# NQX25017A-V1_0_i300-N32WB031.net
KiCad netlist of a schematic drawn in Altium Designer
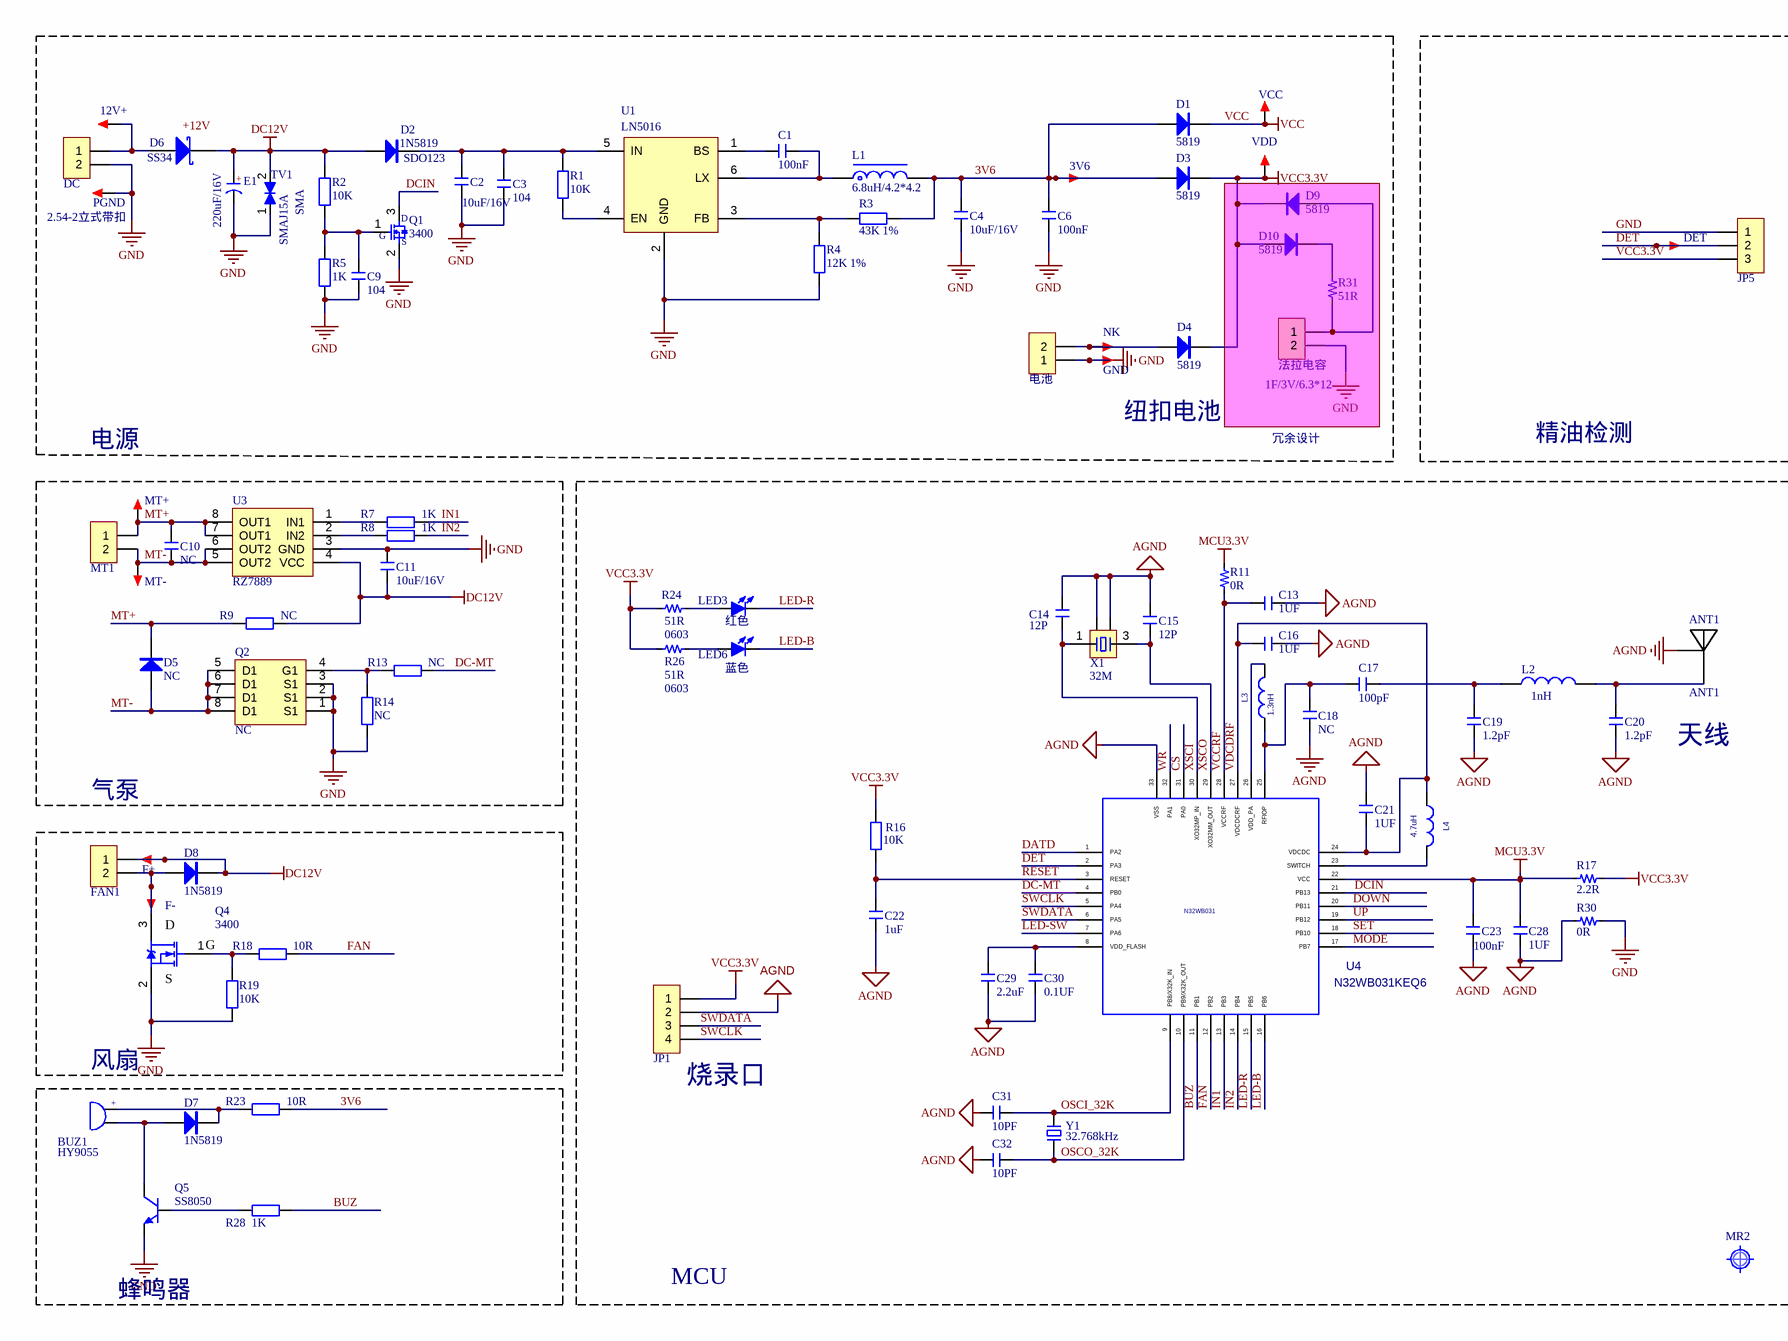
[diagram p0: NQX25017A-V1.0(i300-N32WB031).SchDoc, left]
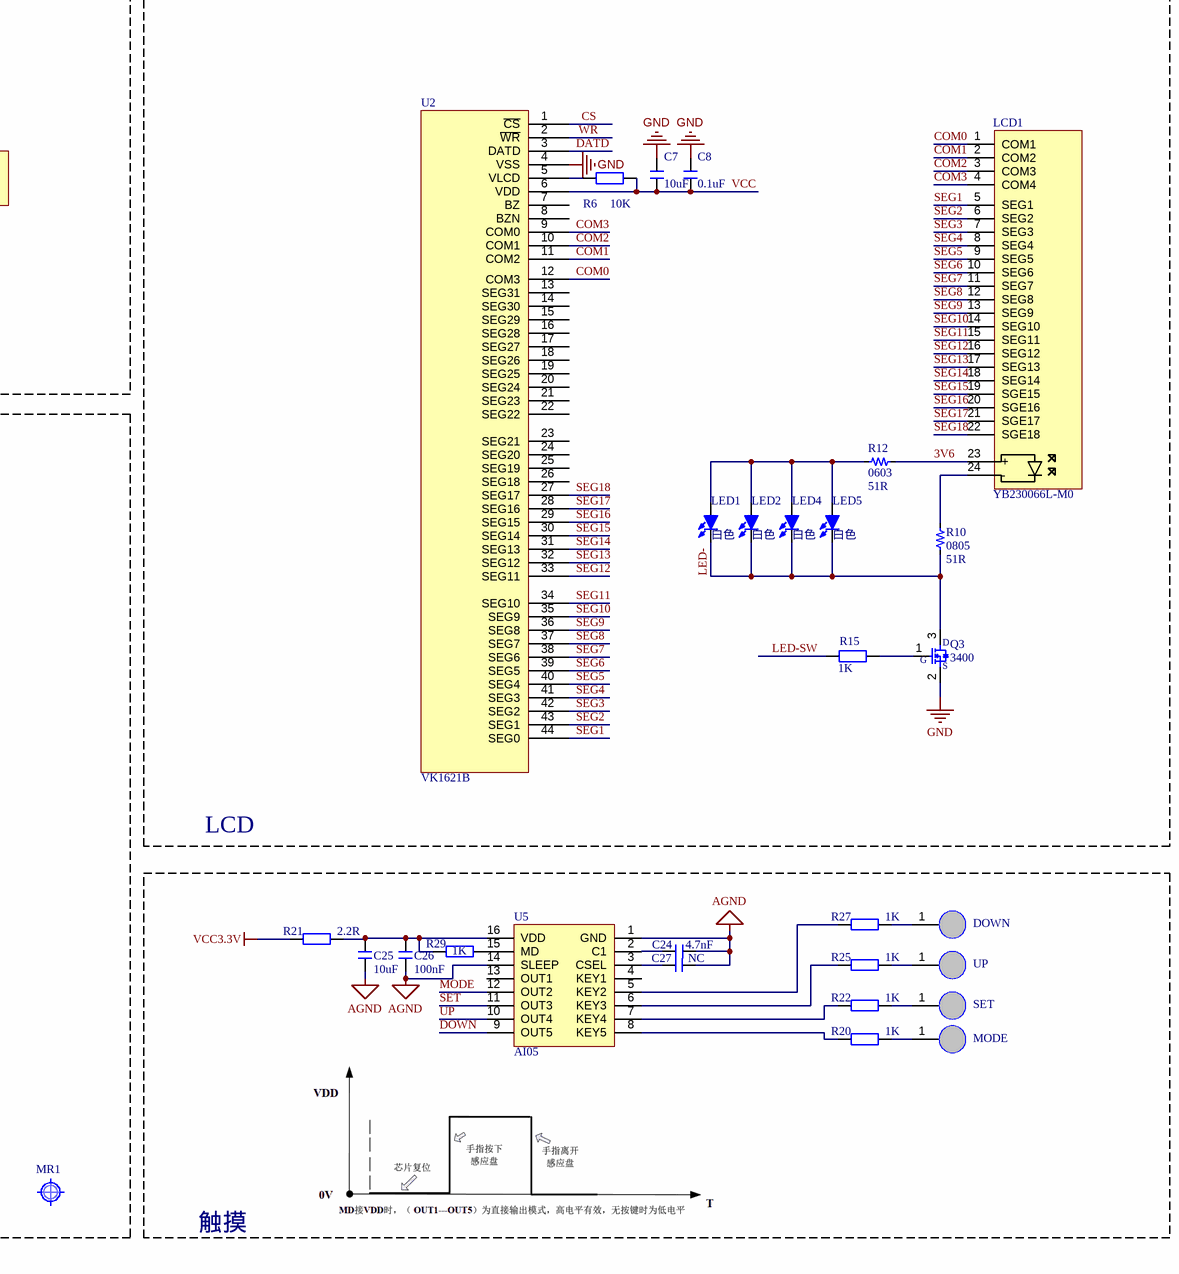
[diagram p1: NQX25017A-V1.0(i300-N32WB031).SchDoc, right]

(export (version "E")
  (design (tool "Eeschema 10.0.6"))
  (components
    (comp (ref "3V6")
      (value "TEST")
      (footprint "TEST 1.2")
      (description "测试点")
      (fields (field (name "版权归属") "封装库来自淘宝 ID：黄晶宝石"))
      (libsource (lib "4.1 - 未分类器件") (part "TEST"))
    )
    (comp (ref "12V+")
      (value "TEST")
      (footprint "TEST 1.2")
      (description "测试点")
      (fields (field (name "版权归属") "封装库来自淘宝 ID：黄晶宝石"))
      (libsource (lib "4.1 - 未分类器件") (part "TEST"))
    )
    (comp (ref "ANT1")
      (value "ANT1")
      (footprint "ANT-BLUE")
      (description "PCB板载天线")
      (fields (field (name "版权归属") "封装库来自淘宝 ID：黄晶宝石"))
      (libsource (lib "1.8 - WiFi天线-SMA射频座") (part "ANT2_1"))
    )
    (comp (ref "BUZ1")
      (value "HY9055")
      (footprint "BEEP 4x9x5.5 - duplicate")
      (description "蜂鸣器")
      (fields (field (name "版权归属") "封装库来自淘宝 ID：黄晶宝石"))
      (libsource (lib "4.1 - 未分类器件") (part "BEEP"))
    )
    (comp (ref "C1")
      (value "100nF")
      (footprint "C0603-T")
      (description "贴片电容")
      (libsource (lib "0.1 - 电阻-电容-电感") (part "C"))
    )
    (comp (ref "C2")
      (value "10uF/16V")
      (footprint "C0603")
      (description "贴片电容")
      (libsource (lib "0.1 - 电阻-电容-电感") (part "C"))
    )
    (comp (ref "C3")
      (value "104")
      (footprint "C0603-T")
      (description "贴片电容")
      (libsource (lib "0.1 - 电阻-电容-电感") (part "C"))
    )
    (comp (ref "C4")
      (value "10uF/16V")
      (footprint "C0805-T")
      (description "贴片电容")
      (libsource (lib "0.1 - 电阻-电容-电感") (part "C"))
    )
    (comp (ref "C6")
      (value "100nF")
      (footprint "C0603-T")
      (description "贴片电容")
      (libsource (lib "0.1 - 电阻-电容-电感") (part "C"))
    )
    (comp (ref "C7")
      (value "10uF")
      (footprint "C0603-T")
      (description "贴片电容")
      (libsource (lib "0.1 - 电阻-电容-电感") (part "C"))
    )
    (comp (ref "C8")
      (value "0.1uF")
      (footprint "C0603-T")
      (description "贴片电容")
      (libsource (lib "0.1 - 电阻-电容-电感") (part "C"))
    )
    (comp (ref "C9")
      (value "104")
      (footprint "C0603-T")
      (description "贴片电容")
      (libsource (lib "0.1 - 电阻-电容-电感") (part "C"))
    )
    (comp (ref "C10")
      (value "NC")
      (footprint "C0603-T")
      (description "贴片电容")
      (libsource (lib "0.1 - 电阻-电容-电感") (part "C"))
    )
    (comp (ref "C11")
      (value "10uF/16V")
      (footprint "C0603")
      (description "贴片电容")
      (libsource (lib "0.1 - 电阻-电容-电感") (part "C"))
    )
    (comp (ref "C13")
      (value "1UF")
      (footprint "C0603-T")
      (description "贴片电容")
      (libsource (lib "0.1 - 电阻-电容-电感") (part "C"))
    )
    (comp (ref "C14")
      (value "12P")
      (footprint "C0603-T")
      (description "贴片电容")
      (libsource (lib "0.1 - 电阻-电容-电感") (part "C"))
    )
    (comp (ref "C15")
      (value "12P")
      (footprint "C0603-T")
      (description "贴片电容")
      (libsource (lib "0.1 - 电阻-电容-电感") (part "C"))
    )
    (comp (ref "C16")
      (value "1UF")
      (footprint "C0603-T")
      (description "贴片电容")
      (libsource (lib "0.1 - 电阻-电容-电感") (part "C"))
    )
    (comp (ref "C17")
      (value "100pF")
      (footprint "C0603-T")
      (description "贴片电容")
      (libsource (lib "0.1 - 电阻-电容-电感") (part "C"))
    )
    (comp (ref "C18")
      (value "NC")
      (footprint "C0603-T")
      (description "贴片电容")
      (libsource (lib "0.1 - 电阻-电容-电感") (part "C"))
    )
    (comp (ref "C19")
      (value "1.2pF")
      (footprint "C0603-T")
      (description "贴片电容")
      (libsource (lib "0.1 - 电阻-电容-电感") (part "C"))
    )
    (comp (ref "C20")
      (value "1.2pF")
      (footprint "C0603-T")
      (description "贴片电容")
      (libsource (lib "0.1 - 电阻-电容-电感") (part "C"))
    )
    (comp (ref "C21")
      (value "1UF")
      (footprint "C0603-T")
      (description "贴片电容")
      (libsource (lib "0.1 - 电阻-电容-电感") (part "C"))
    )
    (comp (ref "C22")
      (value "1uF")
      (footprint "C0603-T")
      (description "贴片电容")
      (libsource (lib "0.1 - 电阻-电容-电感") (part "C"))
    )
    (comp (ref "C23")
      (value "100nF")
      (footprint "C0603-T")
      (description "贴片电容")
      (libsource (lib "0.1 - 电阻-电容-电感") (part "C"))
    )
    (comp (ref "C24")
      (value "4.7nF")
      (footprint "C0603-T")
      (description "贴片电容")
      (libsource (lib "0.1 - 电阻-电容-电感") (part "C"))
    )
    (comp (ref "C25")
      (value "10uF")
      (footprint "C0603-T")
      (description "贴片电容")
      (libsource (lib "0.1 - 电阻-电容-电感") (part "C"))
    )
    (comp (ref "C26")
      (value "100nF")
      (footprint "C0603-T")
      (description "贴片电容")
      (libsource (lib "0.1 - 电阻-电容-电感") (part "C"))
    )
    (comp (ref "C27")
      (value "NC")
      (footprint "C0603-T")
      (description "贴片电容")
      (libsource (lib "0.1 - 电阻-电容-电感") (part "C"))
    )
    (comp (ref "C28")
      (value "1UF")
      (footprint "C0603-T")
      (description "贴片电容")
      (libsource (lib "0.1 - 电阻-电容-电感") (part "C"))
    )
    (comp (ref "C29")
      (value "2.2uF")
      (footprint "C0603-T")
      (description "贴片电容")
      (libsource (lib "0.1 - 电阻-电容-电感") (part "C"))
    )
    (comp (ref "C30")
      (value "0.1UF")
      (footprint "C0603-T")
      (description "贴片电容")
      (libsource (lib "0.1 - 电阻-电容-电感") (part "C"))
    )
    (comp (ref "C31")
      (value "10PF")
      (footprint "C0603-T")
      (description "贴片电容")
      (libsource (lib "0.1 - 电阻-电容-电感") (part "C"))
    )
    (comp (ref "C32")
      (value "10PF")
      (footprint "C0603-T")
      (description "贴片电容")
      (libsource (lib "0.1 - 电阻-电容-电感") (part "C"))
    )
    (comp (ref "D1")
      (value "5819")
      (footprint "SOD-123")
      (description "整流二极管")
      (libsource (lib "0.2 - 二极管-整流桥") (part "1N4007"))
    )
    (comp (ref "D2")
      (value "1N5819")
      (footprint "SOD-123")
      (description "整流二极管")
      (fields (field (name "ALTIUM_VALUE") "SDO123"))
      (libsource (lib "0.2 - 二极管-整流桥") (part "1N4007"))
    )
    (comp (ref "D3")
      (value "5819")
      (footprint "SOD-123")
      (description "整流二极管")
      (libsource (lib "0.2 - 二极管-整流桥") (part "1N4007"))
    )
    (comp (ref "D4")
      (value "5819")
      (footprint "SOD-123")
      (description "整流二极管")
      (libsource (lib "0.2 - 二极管-整流桥") (part "1N4007"))
    )
    (comp (ref "D5")
      (value "NC")
      (footprint "SMA")
      (description "整流二极管")
      (fields (field (name "版权归属") "封装库来自淘宝 ID：黄晶宝石"))
      (libsource (lib "0.2 - 二极管-整流桥") (part "M7"))
    )
    (comp (ref "D6")
      (value "SS34")
      (footprint "SMA")
      (description "肖特基二极管")
      (libsource (lib "0.2 - 二极管-整流桥") (part "SS14"))
    )
    (comp (ref "D7")
      (value "1N5819")
      (footprint "MINI_MELF (LL34)")
      (description "开关二极管")
      (libsource (lib "0.2 - 二极管-整流桥") (part "1N4148"))
    )
    (comp (ref "D8")
      (value "1N5819")
      (footprint "MINI_MELF (LL34)")
      (description "开关二极管")
      (libsource (lib "0.2 - 二极管-整流桥") (part "1N4148"))
    )
    (comp (ref "D9")
      (value "5819")
      (footprint "SOD-123")
      (description "整流二极管")
      (libsource (lib "0.2 - 二极管-整流桥") (part "1N4007"))
    )
    (comp (ref "D10")
      (value "5819")
      (footprint "SOD-123")
      (description "整流二极管")
      (libsource (lib "0.2 - 二极管-整流桥") (part "1N4007"))
    )
    (comp (ref "DC")
      (value "2.54-2立式带扣")
      (footprint "XH2.54-LS-2P")
      (description "2P接插件")
      (fields (field (name "版权归属") "封装库来自淘宝 ID：黄晶宝石"))
      (libsource (lib "5.4 - 接插件-脚距2.54 (100mil) ") (part "Header 2"))
    )
    (comp (ref "DET")
      (value "TEST")
      (footprint "TEST 1.2")
      (description "测试点")
      (fields (field (name "版权归属") "封装库来自淘宝 ID：黄晶宝石"))
      (libsource (lib "4.1 - 未分类器件") (part "TEST"))
    )
    (comp (ref "DOWN")
      (value "12x16")
      (footprint "0.3-6.8-12-8")
      (description "触控弹簧")
      (fields (field (name "版权归属") "封装库来自淘宝 ID：黄晶宝石"))
      (libsource (lib "0.7 - 常用按键-开关") (part "TTS"))
    )
    (comp (ref "E1")
      (value "220uF/16V")
      (footprint "CM D(6.3*7.7)")
      (description "贴片电解电容")
      (fields (field (name "版权归属") "封装库来自淘宝 ID：黄晶宝石"))
      (libsource (lib "0.1 - 电阻-电容-电感") (part "CE_SMD"))
    )
    (comp (ref "F+")
      (value "TEST")
      (footprint "TEST 1.2")
      (description "测试点")
      (fields (field (name "版权归属") "封装库来自淘宝 ID：黄晶宝石"))
      (libsource (lib "4.1 - 未分类器件") (part "TEST"))
    )
    (comp (ref "F-")
      (value "TEST")
      (footprint "TEST 1.2")
      (description "测试点")
      (fields (field (name "版权归属") "封装库来自淘宝 ID：黄晶宝石"))
      (libsource (lib "4.1 - 未分类器件") (part "TEST"))
    )
    (comp (ref "FAN1")
      (value "2.54-2立式带扣")
      (footprint "XH2.54-LS-2P")
      (description "2P接插件")
      (fields (field (name "版权归属") "封装库来自淘宝 ID：黄晶宝石"))
      (libsource (lib "5.4 - 接插件-脚距2.54 (100mil) ") (part "Header 2"))
    )
    (comp (ref "GND")
      (value "TEST")
      (footprint "TEST 1.2")
      (description "测试点")
      (fields (field (name "版权归属") "封装库来自淘宝 ID：黄晶宝石"))
      (libsource (lib "4.1 - 未分类器件") (part "TEST"))
    )
    (comp (ref "JP1")
      (value "HDR-1X4")
      (footprint "CN4P2.0")
      (libsource (lib "5.4 - 接插件-脚距2.54 (100mil) ") (part "Header 4"))
    )
    (comp (ref "JP5")
      (value "1.25X3立贴")
      (footprint "MX 1.25-LS-3P")
      (description "3P接插件")
      (libsource (lib "5.0 - 接插件-脚距1.25") (part "Header 3"))
    )
    (comp (ref "L1")
      (value "6.8uH/4.2*4.2")
      (footprint "L5X5")
      (description "CD系列贴片线绕功率电感")
      (libsource (lib "0.1 - 电阻-电容-电感") (part "L-SMD"))
    )
    (comp (ref "L2")
      (value "1nH")
      (footprint "R0603-T")
      (description "小功率贴片电感")
      (libsource (lib "0.1 - 电阻-电容-电感") (part "L"))
    )
    (comp (ref "L3")
      (value "1.3nH")
      (footprint "R0603-T")
      (description "MOLDED INDUCTOR, 0.5\" PIN SPACING")
      (libsource (lib "*") (part "INDUCTOR_0402"))
    )
    (comp (ref "L4")
      (value "4.7uH")
      (footprint "R0603-T")
      (description "MOLDED INDUCTOR, 0.5\" PIN SPACING")
      (libsource (lib "*") (part "INDUCTOR_0402"))
    )
    (comp (ref "LCD1")
      (value "YB230066L-M0")
      (footprint "YB23006L0-M0")
      (description "YB230066L-M0-22PIN")
      (libsource (lib "0.6 - 数码管-TFT-OLED屏") (part "YB230066L-M0"))
    )
    (comp (ref "LED1")
      (value "白色")
      (footprint "LED 0805G")
      (description "贴片LED")
      (fields (field (name "版权归属") "封装库来自淘宝 ID：黄晶宝石"))
      (libsource (lib "0.3 - LED发光二极管") (part "LED-SMD"))
    )
    (comp (ref "LED2")
      (value "白色")
      (footprint "LED 0805G")
      (description "贴片LED")
      (fields (field (name "版权归属") "封装库来自淘宝 ID：黄晶宝石"))
      (libsource (lib "0.3 - LED发光二极管") (part "LED-SMD"))
    )
    (comp (ref "LED3")
      (value "红色")
      (footprint "LED 0805B")
      (description "贴片LED")
      (fields (field (name "版权归属") "封装库来自淘宝 ID：黄晶宝石"))
      (libsource (lib "0.3 - LED发光二极管") (part "LED-SMD"))
    )
    (comp (ref "LED4")
      (value "白色")
      (footprint "LED 0805G")
      (description "贴片LED")
      (fields (field (name "版权归属") "封装库来自淘宝 ID：黄晶宝石"))
      (libsource (lib "0.3 - LED发光二极管") (part "LED-SMD"))
    )
    (comp (ref "LED5")
      (value "白色")
      (footprint "LED 0805G")
      (description "贴片LED")
      (fields (field (name "版权归属") "封装库来自淘宝 ID：黄晶宝石"))
      (libsource (lib "0.3 - LED发光二极管") (part "LED-SMD"))
    )
    (comp (ref "LED6")
      (value "蓝色")
      (footprint "LED 0805B")
      (description "贴片LED")
      (fields (field (name "版权归属") "封装库来自淘宝 ID：黄晶宝石"))
      (libsource (lib "0.3 - LED发光二极管") (part "LED-SMD"))
    )
    (comp (ref "MODE")
      (value "12x16")
      (footprint "0.3-6.8-12-8")
      (description "触控弹簧")
      (fields (field (name "版权归属") "封装库来自淘宝 ID：黄晶宝石"))
      (libsource (lib "0.7 - 常用按键-开关") (part "TTS"))
    )
    (comp (ref "MR1")
      (value "~")
      (footprint "Mark 1")
      (description "光学定位点")
      (fields (field (name "版权归属") "封装库来自淘宝 ID：黄晶宝石"))
      (libsource (lib "4.1 - 未分类器件") (part "MARK"))
    )
    (comp (ref "MR2")
      (value "~")
      (footprint "Mark 1")
      (description "光学定位点")
      (fields (field (name "版权归属") "封装库来自淘宝 ID：黄晶宝石"))
      (libsource (lib "4.1 - 未分类器件") (part "MARK"))
    )
    (comp (ref "MT+")
      (value "TEST")
      (footprint "TEST 1.2")
      (description "测试点")
      (fields (field (name "版权归属") "封装库来自淘宝 ID：黄晶宝石"))
      (libsource (lib "4.1 - 未分类器件") (part "TEST"))
    )
    (comp (ref "MT-")
      (value "TEST")
      (footprint "TEST 1.2")
      (description "测试点")
      (fields (field (name "版权归属") "封装库来自淘宝 ID：黄晶宝石"))
      (libsource (lib "4.1 - 未分类器件") (part "TEST"))
    )
    (comp (ref "MT1")
      (value "2.54-2立式带扣")
      (footprint "XH2.54-LS-2P")
      (description "2P接插件")
      (fields (field (name "版权归属") "封装库来自淘宝 ID：黄晶宝石"))
      (libsource (lib "5.4 - 接插件-脚距2.54 (100mil) ") (part "Header 2"))
    )
    (comp (ref "NK")
      (value "TEST")
      (footprint "TEST 1.2")
      (description "测试点")
      (fields (field (name "版权归属") "封装库来自淘宝 ID：黄晶宝石"))
      (libsource (lib "4.1 - 未分类器件") (part "TEST"))
    )
    (comp (ref "PGND")
      (value "TEST")
      (footprint "TEST 1.2")
      (description "测试点")
      (fields (field (name "版权归属") "封装库来自淘宝 ID：黄晶宝石"))
      (libsource (lib "4.1 - 未分类器件") (part "TEST"))
    )
    (comp (ref "Q1") (value "3400") (footprint "SOT-23") (libsource (lib "DQ") (part "QMOS-N")))
    (comp (ref "Q2")
      (value "NC")
      (footprint "DFN3X3_8P")
      (description "WSD3050DN NMOS")
      (libsource (lib "0.5 - 场效应管-可控硅") (part "WSD3050DN"))
    )
    (comp (ref "Q3") (value "3400") (footprint "SOT-23") (libsource (lib "DQ") (part "QMOS-N")))
    (comp (ref "Q4")
      (value "3400")
      (footprint "SOT-23")
      (description "N沟道场效应管")
      (libsource (lib "0.5 - 场效应管-可控硅") (part "SI2302"))
    )
    (comp (ref "Q5")
      (value "SS8050")
      (footprint "SOT-23")
      (description "高频放大-NPN型")
      (fields (field (name "版权归属") "封装库来自淘宝 ID：黄晶宝石"))
      (libsource (lib "0.4 - 三极管") (part "8050-SMD"))
    )
    (comp (ref "R1")
      (value "10K")
      (footprint "R0603-T")
      (description "贴片电阻")
      (fields (field (name "版权归属") "来自淘宝 ID：黄晶宝石"))
      (libsource (lib "0.1 - 电阻-电容-电感") (part "R"))
    )
    (comp (ref "R2")
      (value "10K")
      (footprint "R0603-T")
      (description "贴片电阻")
      (fields (field (name "版权归属") "来自淘宝 ID：黄晶宝石"))
      (libsource (lib "0.1 - 电阻-电容-电感") (part "R"))
    )
    (comp (ref "R3")
      (value "43K 1%")
      (footprint "R0603-T")
      (description "贴片电阻")
      (fields (field (name "版权归属") "来自淘宝 ID：黄晶宝石"))
      (libsource (lib "0.1 - 电阻-电容-电感") (part "R"))
    )
    (comp (ref "R4")
      (value "12K 1%")
      (footprint "R0603-T")
      (description "贴片电阻")
      (fields (field (name "版权归属") "来自淘宝 ID：黄晶宝石"))
      (libsource (lib "0.1 - 电阻-电容-电感") (part "R"))
    )
    (comp (ref "R5")
      (value "1K")
      (footprint "R0603-T")
      (description "贴片电阻")
      (fields (field (name "版权归属") "来自淘宝 ID：黄晶宝石"))
      (libsource (lib "0.1 - 电阻-电容-电感") (part "R"))
    )
    (comp (ref "R6")
      (value "10K")
      (footprint "R0603-T")
      (description "贴片电阻")
      (libsource (lib "0.1 - 电阻-电容-电感") (part "R"))
    )
    (comp (ref "R7")
      (value "1K")
      (footprint "R0603-T")
      (description "贴片电阻")
      (fields (field (name "版权归属") "来自淘宝 ID：黄晶宝石"))
      (libsource (lib "0.1 - 电阻-电容-电感") (part "R"))
    )
    (comp (ref "R8")
      (value "1K")
      (footprint "R0603-T")
      (description "贴片电阻")
      (fields (field (name "版权归属") "来自淘宝 ID：黄晶宝石"))
      (libsource (lib "0.1 - 电阻-电容-电感") (part "R"))
    )
    (comp (ref "R9")
      (value "NC")
      (footprint "R1206-T")
      (description "贴片电阻")
      (fields (field (name "版权归属") "来自淘宝 ID：黄晶宝石"))
      (libsource (lib "0.1 - 电阻-电容-电感") (part "R"))
    )
    (comp (ref "R10")
      (value "51R")
      (footprint "R0805-T")
      (description "贴片电阻/51R/±5%/0805/1/8W")
      (fields (field (name "ALTIUM_VALUE") "0805"))
      (libsource (lib "RES") (part "R0805185-51R"))
    )
    (comp (ref "R11") (value "0R") (footprint "R0603-T") (libsource (lib "WEIDAN") (part "Res")))
    (comp (ref "R12")
      (value "51R")
      (footprint "R0603-T")
      (description "贴片电阻/51R/±1%/0603/1/10W")
      (fields (field (name "ALTIUM_VALUE") "0603"))
      (libsource (lib "RES") (part "R0603101-51R"))
    )
    (comp (ref "R13")
      (value "NC")
      (footprint "R0603-T")
      (description "贴片电阻")
      (fields (field (name "版权归属") "来自淘宝 ID：黄晶宝石"))
      (libsource (lib "0.1 - 电阻-电容-电感") (part "R"))
    )
    (comp (ref "R14")
      (value "NC")
      (footprint "R0603-T")
      (description "贴片电阻")
      (fields (field (name "版权归属") "来自淘宝 ID：黄晶宝石"))
      (libsource (lib "0.1 - 电阻-电容-电感") (part "R"))
    )
    (comp (ref "R15")
      (value "1K")
      (footprint "R0603-T")
      (description "贴片电阻")
      (fields (field (name "版权归属") "来自淘宝 ID：黄晶宝石"))
      (libsource (lib "0.1 - 电阻-电容-电感") (part "R"))
    )
    (comp (ref "R16")
      (value "10K")
      (footprint "R0603-T")
      (description "贴片电阻")
      (fields (field (name "版权归属") "来自淘宝 ID：黄晶宝石"))
      (libsource (lib "0.1 - 电阻-电容-电感") (part "R"))
    )
    (comp (ref "R17") (value "2.2R") (footprint "R0603-T") (libsource (lib "WEIDAN") (part "Res")))
    (comp (ref "R18")
      (value "10R")
      (footprint "R0603-T")
      (description "贴片电阻")
      (fields (field (name "版权归属") "来自淘宝 ID：黄晶宝石"))
      (libsource (lib "0.1 - 电阻-电容-电感") (part "R"))
    )
    (comp (ref "R19")
      (value "10K")
      (footprint "R0603-T")
      (description "贴片电阻")
      (fields (field (name "版权归属") "来自淘宝 ID：黄晶宝石"))
      (libsource (lib "0.1 - 电阻-电容-电感") (part "R"))
    )
    (comp (ref "R20")
      (value "1K")
      (footprint "R0603-T")
      (description "贴片电阻")
      (fields (field (name "版权归属") "来自淘宝 ID：黄晶宝石"))
      (libsource (lib "0.1 - 电阻-电容-电感") (part "R"))
    )
    (comp (ref "R21")
      (value "2.2R")
      (footprint "R0603-T")
      (description "贴片电阻")
      (fields (field (name "版权归属") "来自淘宝 ID：黄晶宝石"))
      (libsource (lib "0.1 - 电阻-电容-电感") (part "R"))
    )
    (comp (ref "R22")
      (value "1K")
      (footprint "R0603-T")
      (description "贴片电阻")
      (fields (field (name "版权归属") "来自淘宝 ID：黄晶宝石"))
      (libsource (lib "0.1 - 电阻-电容-电感") (part "R"))
    )
    (comp (ref "R23")
      (value "10R")
      (footprint "R0603-T")
      (description "贴片电阻")
      (fields (field (name "版权归属") "来自淘宝 ID：黄晶宝石"))
      (libsource (lib "0.1 - 电阻-电容-电感") (part "R"))
    )
    (comp (ref "R24")
      (value "51R")
      (footprint "R0603-T")
      (description "贴片电阻/51R/±1%/0603/1/10W")
      (fields (field (name "ALTIUM_VALUE") "0603"))
      (libsource (lib "RES") (part "R0603101-51R"))
    )
    (comp (ref "R25")
      (value "1K")
      (footprint "R0603-T")
      (description "贴片电阻")
      (fields (field (name "版权归属") "来自淘宝 ID：黄晶宝石"))
      (libsource (lib "0.1 - 电阻-电容-电感") (part "R"))
    )
    (comp (ref "R26")
      (value "51R")
      (footprint "R0603-T")
      (description "贴片电阻/51R/±1%/0603/1/10W")
      (fields (field (name "ALTIUM_VALUE") "0603"))
      (libsource (lib "RES") (part "R0603101-51R"))
    )
    (comp (ref "R27")
      (value "1K")
      (footprint "R0603-T")
      (description "贴片电阻")
      (fields (field (name "版权归属") "来自淘宝 ID：黄晶宝石"))
      (libsource (lib "0.1 - 电阻-电容-电感") (part "R"))
    )
    (comp (ref "R28")
      (value "1K")
      (footprint "R0603-T")
      (description "贴片电阻")
      (fields (field (name "版权归属") "来自淘宝 ID：黄晶宝石"))
      (libsource (lib "0.1 - 电阻-电容-电感") (part "R"))
    )
    (comp (ref "R29")
      (value "1K")
      (footprint "R0603-T")
      (description "贴片电阻")
      (fields (field (name "版权归属") "来自淘宝 ID：黄晶宝石"))
      (libsource (lib "0.1 - 电阻-电容-电感") (part "R"))
    )
    (comp (ref "R30") (value "0R") (footprint "R0603-T") (libsource (lib "WEIDAN") (part "Res")))
    (comp (ref "R31") (value "51R") (footprint "R0805-T") (libsource (lib "WEIDAN") (part "Res")))
    (comp (ref "SET")
      (value "12x16")
      (footprint "0.3-6.8-12-8")
      (description "触控弹簧")
      (fields (field (name "版权归属") "封装库来自淘宝 ID：黄晶宝石"))
      (libsource (lib "0.7 - 常用按键-开关") (part "TTS"))
    )
    (comp (ref "TV1")
      (value "SMAJ15A")
      (footprint "SMA")
      (fields (field (name "ALTIUM_VALUE") "SMA"))
      (libsource (lib "DQ") (part "D-TVS-0402"))
    )
    (comp (ref "U1")
      (value "LN5016")
      (footprint "SOT23-6L")
      (description "降压IC,LN5016,SOT23-6 环保")
      (libsource (lib "1.1 - 电源类芯片") (part "LN5016"))
    )
    (comp (ref "U2")
      (value "VK1621B")
      (footprint "LQFP44 10X10_N")
      (description "VK1621B 32*4 液晶驅動 IC")
      (libsource (lib "8.1 - 屏驱芯片") (part "VK1621B"))
    )
    (comp (ref "U3")
      (value "RZ7889")
      (footprint "SOP8_N")
      (description "DC 双向马达驱动电路")
      (libsource (lib "0.5 - 场效应管-可控硅") (part "SS6285L"))
    )
    (comp (ref "U4")
      (value "N32WB031KEQ6")
      (footprint "QFN32_4X4")
      (fields (field (name "ALTIUM_VALUE") "N32WB031"))
      (libsource (lib "*") (part "NS7300_1A_QFN32"))
    )
    (comp (ref "U5")
      (value "AI05")
      (footprint "SOP16")
      (description "AI05 5 键的电容式触摸感应芯片")
      (libsource (lib "8.2 - 触摸芯片") (part "AI05"))
    )
    (comp (ref "UP")
      (value "12x16")
      (footprint "0.3-6.8-12-8")
      (description "触控弹簧")
      (fields (field (name "版权归属") "封装库来自淘宝 ID：黄晶宝石"))
      (libsource (lib "0.7 - 常用按键-开关") (part "TTS"))
    )
    (comp (ref "VCC")
      (value "TEST")
      (footprint "TEST 1.2")
      (description "测试点")
      (fields (field (name "版权归属") "封装库来自淘宝 ID：黄晶宝石"))
      (libsource (lib "4.1 - 未分类器件") (part "TEST"))
    )
    (comp (ref "VDD")
      (value "TEST")
      (footprint "TEST 1.2")
      (description "测试点")
      (fields (field (name "版权归属") "封装库来自淘宝 ID：黄晶宝石"))
      (libsource (lib "4.1 - 未分类器件") (part "TEST"))
    )
    (comp (ref "X1")
      (value "32M")
      (footprint "OSC3225")
      (description "4脚无源晶振(谐振器）")
      (libsource (lib "0.1 - 电阻-电容-电感-保险丝-晶振-晶体-磁珠-电位器-法拉电容-馈通电容") (part "XTAL-4P"))
    )
    (comp (ref "Y1")
      (value "32.768kHz")
      (footprint "OSC-3x8-WI-B")
      (description "2脚无源脚晶振")
      (fields (field (name "版权归属") "封装库来自淘宝卖家 ID：黄晶宝石"))
      (libsource (lib "2.0 - 保险丝-晶振-光耦") (part "XTAL-2P"))
    )
    (comp (ref "法拉电容")
      (value "1F/3V/6.3*12")
      (footprint "CE-2.5*5*11-H")
      (description "2P接插件")
      (fields (field (name "版权归属") "封装库来自淘宝 ID：黄晶宝石"))
      (libsource (lib "5.3 - 接插件-脚距2.0") (part "Header 2"))
    )
    (comp (ref "电池")
      (value "2.0-2立贴无扣")
      (footprint "PH2.0-LS-2P")
      (description "2P接插件")
      (fields (field (name "版权归属") "封装库来自淘宝 ID：黄晶宝石"))
      (libsource (lib "") (part "Header 2_1"))
    )
  )
  (nets
    (net (code "2") (name "/3V6") (class "Default")
      (node (ref "3V6") (pin "1") (pinfunction "1_1") (pintype "passive"))
      (node (ref "C4") (pin "2") (pinfunction "2_2") (pintype "passive"))
      (node (ref "C6") (pin "1") (pinfunction "1_1") (pintype "passive"))
      (node (ref "D1") (pin "1") (pinfunction "A_1") (pintype "passive"))
      (node (ref "D3") (pin "1") (pinfunction "A_1") (pintype "passive"))
      (node (ref "L1") (pin "2") (pinfunction "2_2") (pintype "passive"))
      (node (ref "LCD1") (pin "23") (pinfunction "+_23") (pintype "passive"))
      (node (ref "R12") (pin "2") (pintype "passive"))
      (node (ref "R23") (pin "2") (pinfunction "2_2") (pintype "passive"))
      (node (ref "R3") (pin "2") (pinfunction "2_2") (pintype "passive"))
    )
    (net (code "3") (name "/BUZ") (class "Default")
      (node (ref "R28") (pin "1") (pinfunction "1_1") (pintype "passive"))
      (node (ref "U4") (pin "11") (pinfunction "PB1_11") (pintype "passive"))
    )
    (net (code "4") (name "/COM0") (class "Default")
      (node (ref "LCD1") (pin "1") (pinfunction "COM1_1") (pintype "passive"))
      (node (ref "U2") (pin "12") (pinfunction "COM3_12") (pintype "passive"))
    )
    (net (code "5") (name "/COM1") (class "Default")
      (node (ref "LCD1") (pin "2") (pinfunction "COM2_2") (pintype "passive"))
      (node (ref "U2") (pin "11") (pinfunction "COM2_11") (pintype "passive"))
    )
    (net (code "6") (name "/COM2") (class "Default")
      (node (ref "LCD1") (pin "3") (pinfunction "COM3_3") (pintype "passive"))
      (node (ref "U2") (pin "10") (pinfunction "COM1_10") (pintype "passive"))
    )
    (net (code "7") (name "/COM3") (class "Default")
      (node (ref "LCD1") (pin "4") (pinfunction "COM4_4") (pintype "passive"))
      (node (ref "U2") (pin "9") (pinfunction "COM0_9") (pintype "passive"))
    )
    (net (code "8") (name "/CS") (class "Default")
      (node (ref "U2") (pin "1") (pinfunction "~{CS}_1") (pintype "passive"))
      (node (ref "U4") (pin "31") (pinfunction "PA0_31") (pintype "passive"))
    )
    (net (code "9") (name "/DATD") (class "Default")
      (node (ref "U2") (pin "3") (pinfunction "DATD_3") (pintype "passive"))
      (node (ref "U4") (pin "1") (pinfunction "PA2_1") (pintype "passive"))
    )
    (net (code "10") (name "/DC-MT") (class "Default")
      (node (ref "R13") (pin "2") (pinfunction "2_2") (pintype "passive"))
      (node (ref "U4") (pin "4") (pinfunction "PB0_4") (pintype "passive"))
    )
    (net (code "11") (name "/DCIN") (class "Default")
      (node (ref "Q1") (pin "3") (pinfunction "D_3") (pintype "passive"))
      (node (ref "U4") (pin "21") (pinfunction "PB13_21") (pintype "passive"))
    )
    (net (code "12") (name "/DET") (class "Default")
      (node (ref "DET") (pin "1") (pinfunction "1_1") (pintype "passive"))
      (node (ref "JP5") (pin "2") (pinfunction "2_2") (pintype "passive"))
      (node (ref "U4") (pin "2") (pinfunction "PA3_2") (pintype "passive"))
    )
    (net (code "13") (name "/DOWN") (class "Default")
      (node (ref "U4") (pin "20") (pinfunction "PB11_20") (pintype "passive"))
      (node (ref "U5") (pin "9") (pinfunction "OUT5_9") (pintype "passive"))
    )
    (net (code "14") (name "/FAN") (class "Default")
      (node (ref "R18") (pin "2") (pinfunction "2_2") (pintype "passive"))
      (node (ref "U4") (pin "12") (pinfunction "PB2_12") (pintype "passive"))
    )
    (net (code "15") (name "/IN1") (class "Default")
      (node (ref "R7") (pin "2") (pinfunction "2_2") (pintype "passive"))
      (node (ref "U4") (pin "13") (pinfunction "PB3_13") (pintype "passive"))
    )
    (net (code "16") (name "/IN2") (class "Default")
      (node (ref "R8") (pin "2") (pinfunction "2_2") (pintype "passive"))
      (node (ref "U4") (pin "14") (pinfunction "PB4_14") (pintype "passive"))
    )
    (net (code "17") (name "/LED-") (class "Default")
      (node (ref "LED1") (pin "2") (pinfunction "K_2") (pintype "passive"))
      (node (ref "LED2") (pin "2") (pinfunction "K_2") (pintype "passive"))
      (node (ref "LED4") (pin "2") (pinfunction "K_2") (pintype "passive"))
      (node (ref "LED5") (pin "2") (pinfunction "K_2") (pintype "passive"))
      (node (ref "Q3") (pin "3") (pinfunction "D_3") (pintype "passive"))
      (node (ref "R10") (pin "1") (pintype "passive"))
    )
    (net (code "18") (name "/LED-B") (class "Default")
      (node (ref "LED6") (pin "2") (pinfunction "K_2") (pintype "passive"))
      (node (ref "U4") (pin "16") (pinfunction "PB6_16") (pintype "passive"))
    )
    (net (code "19") (name "/LED-R") (class "Default")
      (node (ref "LED3") (pin "2") (pinfunction "K_2") (pintype "passive"))
      (node (ref "U4") (pin "15") (pinfunction "PB5_15") (pintype "passive"))
    )
    (net (code "20") (name "/LED-SW") (class "Default")
      (node (ref "R15") (pin "2") (pinfunction "2_2") (pintype "passive"))
      (node (ref "U4") (pin "7") (pinfunction "PA6_7") (pintype "passive"))
    )
    (net (code "21") (name "/MODE") (class "Default")
      (node (ref "U4") (pin "17") (pinfunction "PB7_17") (pintype "passive"))
      (node (ref "U5") (pin "12") (pinfunction "OUT2_12") (pintype "passive"))
    )
    (net (code "22") (name "/MT+") (class "Default")
      (node (ref "C10") (pin "2") (pinfunction "2_2") (pintype "passive"))
      (node (ref "D5") (pin "2") (pinfunction "K_2") (pintype "passive"))
      (node (ref "MT+") (pin "1") (pinfunction "1_1") (pintype "passive"))
      (node (ref "MT1") (pin "1") (pinfunction "1_1") (pintype "passive"))
      (node (ref "R9") (pin "1") (pinfunction "1_1") (pintype "passive"))
      (node (ref "U3") (pin "7") (pinfunction "OUT1_7") (pintype "passive"))
      (node (ref "U3") (pin "8") (pinfunction "OUT1_8") (pintype "passive"))
    )
    (net (code "23") (name "/MT-") (class "Default")
      (node (ref "C10") (pin "1") (pinfunction "1_1") (pintype "passive"))
      (node (ref "D5") (pin "1") (pinfunction "A_1") (pintype "passive"))
      (node (ref "MT-") (pin "1") (pinfunction "1_1") (pintype "passive"))
      (node (ref "MT1") (pin "2") (pinfunction "2_2") (pintype "passive"))
      (node (ref "Q2") (pin "5") (pinfunction "D1_5") (pintype "passive"))
      (node (ref "Q2") (pin "6") (pinfunction "D1_6") (pintype "passive"))
      (node (ref "Q2") (pin "7") (pinfunction "D1_7") (pintype "passive"))
      (node (ref "Q2") (pin "8") (pinfunction "D1_8") (pintype "passive"))
      (node (ref "U3") (pin "5") (pinfunction "OUT2_5") (pintype "passive"))
      (node (ref "U3") (pin "6") (pinfunction "OUT2_6") (pintype "passive"))
    )
    (net (code "24") (name "/OSCI_32K") (class "Default")
      (node (ref "C31") (pin "2") (pinfunction "2_2") (pintype "passive"))
      (node (ref "U4") (pin "9") (pinfunction "PB8/X32K_IN_9") (pintype "passive"))
      (node (ref "Y1") (pin "1") (pinfunction "1_1") (pintype "passive"))
    )
    (net (code "25") (name "/OSCO_32K") (class "Default")
      (node (ref "C32") (pin "2") (pinfunction "2_2") (pintype "passive"))
      (node (ref "U4") (pin "10") (pinfunction "PB9/X32K_OUT_10") (pintype "passive"))
      (node (ref "Y1") (pin "2") (pinfunction "2_2") (pintype "passive"))
    )
    (net (code "26") (name "/RESET") (class "Default")
      (node (ref "C22") (pin "2") (pinfunction "2_2") (pintype "passive"))
      (node (ref "R16") (pin "2") (pinfunction "2_2") (pintype "passive"))
      (node (ref "U4") (pin "3") (pinfunction "RESET_3") (pintype "passive"))
    )
    (net (code "27") (name "/SEG1") (class "Default")
      (node (ref "LCD1") (pin "5") (pinfunction "SEG1_5") (pintype "passive"))
      (node (ref "U2") (pin "44") (pinfunction "SEG0_44") (pintype "passive"))
    )
    (net (code "28") (name "/SEG2") (class "Default")
      (node (ref "LCD1") (pin "6") (pinfunction "SEG2_6") (pintype "passive"))
      (node (ref "U2") (pin "43") (pinfunction "SEG1_43") (pintype "passive"))
    )
    (net (code "29") (name "/SEG3") (class "Default")
      (node (ref "LCD1") (pin "7") (pinfunction "SEG3_7") (pintype "passive"))
      (node (ref "U2") (pin "42") (pinfunction "SEG2_42") (pintype "passive"))
    )
    (net (code "30") (name "/SEG4") (class "Default")
      (node (ref "LCD1") (pin "8") (pinfunction "SEG4_8") (pintype "passive"))
      (node (ref "U2") (pin "41") (pinfunction "SEG3_41") (pintype "passive"))
    )
    (net (code "31") (name "/SEG5") (class "Default")
      (node (ref "LCD1") (pin "9") (pinfunction "SEG5_9") (pintype "passive"))
      (node (ref "U2") (pin "40") (pinfunction "SEG4_40") (pintype "passive"))
    )
    (net (code "32") (name "/SEG6") (class "Default")
      (node (ref "LCD1") (pin "10") (pinfunction "SEG6_10") (pintype "passive"))
      (node (ref "U2") (pin "39") (pinfunction "SEG5_39") (pintype "passive"))
    )
    (net (code "33") (name "/SEG7") (class "Default")
      (node (ref "LCD1") (pin "11") (pinfunction "SEG7_11") (pintype "passive"))
      (node (ref "U2") (pin "38") (pinfunction "SEG6_38") (pintype "passive"))
    )
    (net (code "34") (name "/SEG8") (class "Default")
      (node (ref "LCD1") (pin "12") (pinfunction "SEG8_12") (pintype "passive"))
      (node (ref "U2") (pin "37") (pinfunction "SEG7_37") (pintype "passive"))
    )
    (net (code "35") (name "/SEG9") (class "Default")
      (node (ref "LCD1") (pin "13") (pinfunction "SEG9_13") (pintype "passive"))
      (node (ref "U2") (pin "36") (pinfunction "SEG8_36") (pintype "passive"))
    )
    (net (code "36") (name "/SEG10") (class "Default")
      (node (ref "LCD1") (pin "14") (pinfunction "SEG10_14") (pintype "passive"))
      (node (ref "U2") (pin "35") (pinfunction "SEG9_35") (pintype "passive"))
    )
    (net (code "37") (name "/SEG11") (class "Default")
      (node (ref "LCD1") (pin "15") (pinfunction "SEG11_15") (pintype "passive"))
      (node (ref "U2") (pin "34") (pinfunction "SEG10_34") (pintype "passive"))
    )
    (net (code "38") (name "/SEG12") (class "Default")
      (node (ref "LCD1") (pin "16") (pinfunction "SEG12_16") (pintype "passive"))
      (node (ref "U2") (pin "33") (pinfunction "SEG11_33") (pintype "passive"))
    )
    (net (code "39") (name "/SEG13") (class "Default")
      (node (ref "LCD1") (pin "17") (pinfunction "SEG13_17") (pintype "passive"))
      (node (ref "U2") (pin "32") (pinfunction "SEG12_32") (pintype "passive"))
    )
    (net (code "40") (name "/SEG14") (class "Default")
      (node (ref "LCD1") (pin "18") (pinfunction "SEG14_18") (pintype "passive"))
      (node (ref "U2") (pin "31") (pinfunction "SEG13_31") (pintype "passive"))
    )
    (net (code "41") (name "/SEG15") (class "Default")
      (node (ref "LCD1") (pin "19") (pinfunction "SGE15_19") (pintype "passive"))
      (node (ref "U2") (pin "30") (pinfunction "SEG14_30") (pintype "passive"))
    )
    (net (code "42") (name "/SEG16") (class "Default")
      (node (ref "LCD1") (pin "20") (pinfunction "SGE16_20") (pintype "passive"))
      (node (ref "U2") (pin "29") (pinfunction "SEG15_29") (pintype "passive"))
    )
    (net (code "43") (name "/SEG17") (class "Default")
      (node (ref "LCD1") (pin "21") (pinfunction "SGE17_21") (pintype "passive"))
      (node (ref "U2") (pin "28") (pinfunction "SEG16_28") (pintype "passive"))
    )
    (net (code "44") (name "/SEG18") (class "Default")
      (node (ref "LCD1") (pin "22") (pinfunction "SGE18_22") (pintype "passive"))
      (node (ref "U2") (pin "27") (pinfunction "SEG17_27") (pintype "passive"))
    )
    (net (code "45") (name "/SET") (class "Default")
      (node (ref "U4") (pin "18") (pinfunction "PB10_18") (pintype "passive"))
      (node (ref "U5") (pin "11") (pinfunction "OUT3_11") (pintype "passive"))
    )
    (net (code "46") (name "/SWCLK") (class "Default")
      (node (ref "JP1") (pin "4") (pinfunction "4_4") (pintype "passive"))
      (node (ref "U4") (pin "5") (pinfunction "PA4_5") (pintype "passive"))
    )
    (net (code "47") (name "/SWDATA") (class "Default")
      (node (ref "JP1") (pin "3") (pinfunction "3_3") (pintype "passive"))
      (node (ref "U4") (pin "6") (pinfunction "PA5_6") (pintype "passive"))
    )
    (net (code "48") (name "/UP") (class "Default")
      (node (ref "U4") (pin "19") (pinfunction "PB12_19") (pintype "passive"))
      (node (ref "U5") (pin "10") (pinfunction "OUT4_10") (pintype "passive"))
    )
    (net (code "49") (name "/VCCRF") (class "Default")
      (node (ref "C13") (pin "2") (pinfunction "2_2") (pintype "passive"))
      (node (ref "R11") (pin "1") (pinfunction "1_1") (pintype "passive"))
      (node (ref "U4") (pin "28") (pinfunction "VCCRF_28") (pintype "passive"))
    )
    (net (code "50") (name "/VDCDRF") (class "Default")
      (node (ref "C16") (pin "2") (pinfunction "2_2") (pintype "passive"))
      (node (ref "C21") (pin "2") (pinfunction "2_2") (pintype "passive"))
      (node (ref "L4") (pin "2") (pinfunction "2_2") (pintype "passive"))
      (node (ref "U4") (pin "24") (pinfunction "VDCDC_24") (pintype "passive"))
      (node (ref "U4") (pin "27") (pinfunction "VDCDCRF_27") (pintype "passive"))
    )
    (net (code "51") (name "/WR") (class "Default")
      (node (ref "U2") (pin "2") (pinfunction "~{WR}_2") (pintype "passive"))
      (node (ref "U4") (pin "32") (pinfunction "PA1_32") (pintype "passive"))
    )
    (net (code "52") (name "/XSCI") (class "Default")
      (node (ref "C14") (pin "1") (pinfunction "1_1") (pintype "passive"))
      (node (ref "U4") (pin "30") (pinfunction "XO32MP_IN_30") (pintype "passive"))
      (node (ref "X1") (pin "1") (pinfunction "1_1") (pintype "passive"))
    )
    (net (code "53") (name "/XSCO") (class "Default")
      (node (ref "C15") (pin "1") (pinfunction "1_1") (pintype "passive"))
      (node (ref "U4") (pin "29") (pinfunction "XO32MM_OUT_29") (pintype "passive"))
      (node (ref "X1") (pin "3") (pinfunction "3_3") (pintype "passive"))
    )
    (net (code "54") (name "AGND") (class "Default")
      (node (ref "ANT1") (pin "2") (pinfunction "2_2") (pintype "passive"))
      (node (ref "C13") (pin "1") (pinfunction "1_1") (pintype "passive"))
      (node (ref "C14") (pin "2") (pinfunction "2_2") (pintype "passive"))
      (node (ref "C15") (pin "2") (pinfunction "2_2") (pintype "passive"))
      (node (ref "C16") (pin "1") (pinfunction "1_1") (pintype "passive"))
      (node (ref "C18") (pin "1") (pinfunction "1_1") (pintype "passive"))
      (node (ref "C19") (pin "1") (pinfunction "1_1") (pintype "passive"))
      (node (ref "C20") (pin "1") (pinfunction "1_1") (pintype "passive"))
      (node (ref "C21") (pin "1") (pinfunction "1_1") (pintype "passive"))
      (node (ref "C22") (pin "1") (pinfunction "1_1") (pintype "passive"))
      (node (ref "C23") (pin "2") (pinfunction "2_2") (pintype "passive"))
      (node (ref "C24") (pin "2") (pinfunction "2_2") (pintype "passive"))
      (node (ref "C25") (pin "2") (pinfunction "2_2") (pintype "passive"))
      (node (ref "C26") (pin "2") (pinfunction "2_2") (pintype "passive"))
      (node (ref "C27") (pin "2") (pinfunction "2_2") (pintype "passive"))
      (node (ref "C28") (pin "2") (pinfunction "2_2") (pintype "passive"))
      (node (ref "C29") (pin "1") (pinfunction "1_1") (pintype "passive"))
      (node (ref "C30") (pin "2") (pinfunction "2_2") (pintype "passive"))
      (node (ref "C31") (pin "1") (pinfunction "1_1") (pintype "passive"))
      (node (ref "C32") (pin "1") (pinfunction "1_1") (pintype "passive"))
      (node (ref "JP1") (pin "2") (pinfunction "2_2") (pintype "passive"))
      (node (ref "R30") (pin "2") (pinfunction "2_2") (pintype "passive"))
      (node (ref "U4") (pin "33") (pinfunction "VSS_33") (pintype "passive"))
      (node (ref "U5") (pin "1") (pinfunction "GND_1") (pintype "passive"))
      (node (ref "U5") (pin "14") (pinfunction "SLEEP_14") (pintype "passive"))
      (node (ref "X1") (pin "2") (pinfunction "2_2") (pintype "passive"))
      (node (ref "X1") (pin "4") (pinfunction "4_4") (pintype "passive"))
    )
    (net (code "55") (name "DC12V") (class "Default")
      (node (ref "C11") (pin "1") (pinfunction "1_1") (pintype "passive"))
      (node (ref "D2") (pin "1") (pinfunction "A_1") (pintype "passive"))
      (node (ref "D6") (pin "2") (pinfunction "K_2") (pintype "passive"))
      (node (ref "D8") (pin "2") (pinfunction "K_2") (pintype "passive"))
      (node (ref "E1") (pin "1") (pinfunction "A_1") (pintype "passive"))
      (node (ref "F+") (pin "1") (pinfunction "1_1") (pintype "passive"))
      (node (ref "FAN1") (pin "1") (pinfunction "1_1") (pintype "passive"))
      (node (ref "R2") (pin "1") (pinfunction "1_1") (pintype "passive"))
      (node (ref "R9") (pin "2") (pinfunction "2_2") (pintype "passive"))
      (node (ref "TV1") (pin "2") (pinfunction "k_2") (pintype "passive"))
      (node (ref "U3") (pin "4") (pinfunction "VCC_4") (pintype "passive"))
    )
    (net (code "56") (name "GND") (class "Default")
      (node (ref "C11") (pin "2") (pinfunction "2_2") (pintype "passive"))
      (node (ref "C2") (pin "1") (pinfunction "1_1") (pintype "passive"))
      (node (ref "C3") (pin "1") (pinfunction "1_1") (pintype "passive"))
      (node (ref "C4") (pin "1") (pinfunction "1_1") (pintype "passive"))
      (node (ref "C6") (pin "2") (pinfunction "2_2") (pintype "passive"))
      (node (ref "C7") (pin "1") (pinfunction "1_1") (pintype "passive"))
      (node (ref "C8") (pin "1") (pinfunction "1_1") (pintype "passive"))
      (node (ref "C9") (pin "1") (pinfunction "1_1") (pintype "passive"))
      (node (ref "DC") (pin "2") (pinfunction "2_2") (pintype "passive"))
      (node (ref "E1") (pin "2") (pinfunction "K_2") (pintype "passive"))
      (node (ref "GND") (pin "1") (pinfunction "1_1") (pintype "passive"))
      (node (ref "JP5") (pin "1") (pinfunction "1_1") (pintype "passive"))
      (node (ref "PGND") (pin "1") (pinfunction "1_1") (pintype "passive"))
      (node (ref "Q1") (pin "2") (pinfunction "S_2") (pintype "passive"))
      (node (ref "Q2") (pin "1") (pinfunction "S1_1") (pintype "passive"))
      (node (ref "Q2") (pin "2") (pinfunction "S1_2") (pintype "passive"))
      (node (ref "Q2") (pin "3") (pinfunction "S1_3") (pintype "passive"))
      (node (ref "Q3") (pin "2") (pinfunction "S_2") (pintype "passive"))
      (node (ref "Q4") (pin "2") (pinfunction "S_2") (pintype "passive"))
      (node (ref "Q5") (pin "2") (pinfunction "E_2") (pintype "passive"))
      (node (ref "R14") (pin "1") (pinfunction "1_1") (pintype "passive"))
      (node (ref "R19") (pin "1") (pinfunction "1_1") (pintype "passive"))
      (node (ref "R30") (pin "1") (pinfunction "1_1") (pintype "passive"))
      (node (ref "R4") (pin "1") (pinfunction "1_1") (pintype "passive"))
      (node (ref "R5") (pin "1") (pinfunction "1_1") (pintype "passive"))
      (node (ref "TV1") (pin "1") (pinfunction "a_1") (pintype "passive"))
      (node (ref "U1") (pin "2") (pinfunction "GND_2") (pintype "passive"))
      (node (ref "U2") (pin "4") (pinfunction "VSS_4") (pintype "passive"))
      (node (ref "U3") (pin "3") (pinfunction "GND_3") (pintype "passive"))
      (node (ref "法拉电容") (pin "2") (pinfunction "2_2") (pintype "passive"))
      (node (ref "电池") (pin "1") (pinfunction "1_1") (pintype "passive"))
    )
    (net (code "57") (name "MCU3.3V") (class "Default")
      (node (ref "C23") (pin "1") (pinfunction "1_1") (pintype "passive"))
      (node (ref "C28") (pin "1") (pinfunction "1_1") (pintype "passive"))
      (node (ref "R11") (pin "2") (pinfunction "2_2") (pintype "passive"))
      (node (ref "R17") (pin "2") (pinfunction "2_2") (pintype "passive"))
      (node (ref "U4") (pin "22") (pinfunction "VCC_22") (pintype "passive"))
    )
    (net (code "58") (name "Net-(ANT1-Pad1)") (class "Default")
      (node (ref "ANT1") (pin "1") (pinfunction "1_1") (pintype "passive"))
      (node (ref "C20") (pin "2") (pinfunction "2_2") (pintype "passive"))
      (node (ref "L2") (pin "2") (pinfunction "2_2") (pintype "passive"))
    )
    (net (code "59") (name "Net-(C17-Pad1)") (class "Default")
      (node (ref "C17") (pin "1") (pinfunction "1_1") (pintype "passive"))
      (node (ref "C19") (pin "2") (pinfunction "2_2") (pintype "passive"))
      (node (ref "L2") (pin "1") (pinfunction "1_1") (pintype "passive"))
    )
    (net (code "60") (name "Net-(D2-K)") (class "Default")
      (node (ref "C2") (pin "2") (pinfunction "2_2") (pintype "passive"))
      (node (ref "C3") (pin "2") (pinfunction "2_2") (pintype "passive"))
      (node (ref "D2") (pin "2") (pinfunction "K_2") (pintype "passive"))
      (node (ref "R1") (pin "1") (pinfunction "1_1") (pintype "passive"))
      (node (ref "U1") (pin "5") (pinfunction "IN_5") (pintype "passive"))
    )
    (net (code "61") (name "Net-(D4-A)") (class "Default")
      (node (ref "D4") (pin "1") (pinfunction "A_1") (pintype "passive"))
      (node (ref "NK") (pin "1") (pinfunction "1_1") (pintype "passive"))
      (node (ref "电池") (pin "2") (pinfunction "2_2") (pintype "passive"))
    )
    (net (code "62") (name "Net-(D6-A)") (class "Default")
      (node (ref "12V+") (pin "1") (pinfunction "1_1") (pintype "passive"))
      (node (ref "D6") (pin "1") (pinfunction "A_1") (pintype "passive"))
      (node (ref "DC") (pin "1") (pinfunction "1_1") (pintype "passive"))
    )
    (net (code "63") (name "Net-(D7-A)") (class "Default")
      (node (ref "BUZ1") (pin "2") (pinfunction "2_2") (pintype "passive"))
      (node (ref "D7") (pin "1") (pinfunction "A_1") (pintype "passive"))
      (node (ref "Q5") (pin "3") (pinfunction "C_3") (pintype "passive"))
    )
    (net (code "64") (name "Net-(D7-K)") (class "Default")
      (node (ref "BUZ1") (pin "1") (pinfunction "1_1") (pintype "passive"))
      (node (ref "D7") (pin "2") (pinfunction "K_2") (pintype "passive"))
      (node (ref "R23") (pin "1") (pinfunction "1_1") (pintype "passive"))
    )
    (net (code "65") (name "Net-(D8-A)") (class "Default")
      (node (ref "D8") (pin "1") (pinfunction "A_1") (pintype "passive"))
      (node (ref "F-") (pin "1") (pinfunction "1_1") (pintype "passive"))
      (node (ref "FAN1") (pin "2") (pinfunction "2_2") (pintype "passive"))
      (node (ref "Q4") (pin "3") (pinfunction "D_3") (pintype "passive"))
    )
    (net (code "66") (name "Net-(D9-A)") (class "Default")
      (node (ref "D9") (pin "1") (pinfunction "A_1") (pintype "passive"))
      (node (ref "R31") (pin "1") (pinfunction "1_1") (pintype "passive"))
      (node (ref "法拉电容") (pin "1") (pinfunction "1_1") (pintype "passive"))
    )
    (net (code "67") (name "Net-(D10-K)") (class "Default")
      (node (ref "D10") (pin "2") (pinfunction "K_2") (pintype "passive"))
      (node (ref "R31") (pin "2") (pinfunction "2_2") (pintype "passive"))
    )
    (net (code "68") (name "Net-(DOWN-Pad1)") (class "Default")
      (node (ref "DOWN") (pin "1") (pinfunction "1_1") (pintype "passive"))
      (node (ref "R27") (pin "2") (pinfunction "2_2") (pintype "passive"))
    )
    (net (code "69") (name "Net-(LCD1--)") (class "Default")
      (node (ref "LCD1") (pin "24") (pinfunction "-_24") (pintype "passive"))
      (node (ref "R10") (pin "2") (pintype "passive"))
    )
    (net (code "70") (name "Net-(LED1-A)") (class "Default")
      (node (ref "LED1") (pin "1") (pinfunction "A_1") (pintype "passive"))
      (node (ref "LED2") (pin "1") (pinfunction "A_1") (pintype "passive"))
      (node (ref "LED4") (pin "1") (pinfunction "A_1") (pintype "passive"))
      (node (ref "LED5") (pin "1") (pinfunction "A_1") (pintype "passive"))
      (node (ref "R12") (pin "1") (pintype "passive"))
    )
    (net (code "71") (name "Net-(LED3-A)") (class "Default")
      (node (ref "LED3") (pin "1") (pinfunction "A_1") (pintype "passive"))
      (node (ref "R24") (pin "2") (pintype "passive"))
    )
    (net (code "72") (name "Net-(LED6-A)") (class "Default")
      (node (ref "LED6") (pin "1") (pinfunction "A_1") (pintype "passive"))
      (node (ref "R26") (pin "2") (pintype "passive"))
    )
    (net (code "73") (name "Net-(MODE-Pad1)") (class "Default")
      (node (ref "MODE") (pin "1") (pinfunction "1_1") (pintype "passive"))
      (node (ref "R20") (pin "2") (pinfunction "2_2") (pintype "passive"))
    )
    (net (code "74") (name "Net-(Q1-G)") (class "Default")
      (node (ref "C9") (pin "2") (pinfunction "2_2") (pintype "passive"))
      (node (ref "Q1") (pin "1") (pinfunction "G_1") (pintype "passive"))
      (node (ref "R2") (pin "2") (pinfunction "2_2") (pintype "passive"))
      (node (ref "R5") (pin "2") (pinfunction "2_2") (pintype "passive"))
    )
    (net (code "75") (name "Net-(Q2-G1)") (class "Default")
      (node (ref "Q2") (pin "4") (pinfunction "G1_4") (pintype "passive"))
      (node (ref "R13") (pin "1") (pinfunction "1_1") (pintype "passive"))
      (node (ref "R14") (pin "2") (pinfunction "2_2") (pintype "passive"))
    )
    (net (code "76") (name "Net-(Q3-G)") (class "Default")
      (node (ref "Q3") (pin "1") (pinfunction "G_1") (pintype "passive"))
      (node (ref "R15") (pin "1") (pinfunction "1_1") (pintype "passive"))
    )
    (net (code "77") (name "Net-(Q4-G)") (class "Default")
      (node (ref "Q4") (pin "1") (pinfunction "G_1") (pintype "passive"))
      (node (ref "R18") (pin "1") (pinfunction "1_1") (pintype "passive"))
      (node (ref "R19") (pin "2") (pinfunction "2_2") (pintype "passive"))
    )
    (net (code "78") (name "Net-(Q5-B)") (class "Default")
      (node (ref "Q5") (pin "1") (pinfunction "B_1") (pintype "passive"))
      (node (ref "R28") (pin "2") (pinfunction "2_2") (pintype "passive"))
    )
    (net (code "79") (name "Net-(R22-Pad2)") (class "Default")
      (node (ref "R22") (pin "2") (pinfunction "2_2") (pintype "passive"))
      (node (ref "SET") (pin "1") (pinfunction "1_1") (pintype "passive"))
    )
    (net (code "80") (name "Net-(R25-Pad2)") (class "Default")
      (node (ref "R25") (pin "2") (pinfunction "2_2") (pintype "passive"))
      (node (ref "UP") (pin "1") (pinfunction "1_1") (pintype "passive"))
    )
    (net (code "81") (name "Net-(U1-BS)") (class "Default")
      (node (ref "C1") (pin "2") (pinfunction "2_2") (pintype "passive"))
      (node (ref "U1") (pin "1") (pinfunction "BS_1") (pintype "passive"))
    )
    (net (code "82") (name "Net-(U1-EN)") (class "Default")
      (node (ref "R1") (pin "2") (pinfunction "2_2") (pintype "passive"))
      (node (ref "U1") (pin "4") (pinfunction "EN_4") (pintype "passive"))
    )
    (net (code "83") (name "Net-(U1-FB)") (class "Default")
      (node (ref "R3") (pin "1") (pinfunction "1_1") (pintype "passive"))
      (node (ref "R4") (pin "2") (pinfunction "2_2") (pintype "passive"))
      (node (ref "U1") (pin "3") (pinfunction "FB_3") (pintype "passive"))
    )
    (net (code "84") (name "Net-(U1-LX)") (class "Default")
      (node (ref "C1") (pin "1") (pinfunction "1_1") (pintype "passive"))
      (node (ref "L1") (pin "1") (pinfunction "1_1") (pintype "passive"))
      (node (ref "U1") (pin "6") (pinfunction "LX_6") (pintype "passive"))
    )
    (net (code "85") (name "Net-(U2-VLCD)") (class "Default")
      (node (ref "R6") (pin "2") (pinfunction "2_2") (pintype "passive"))
      (node (ref "U2") (pin "5") (pinfunction "VLCD_5") (pintype "passive"))
    )
    (net (code "86") (name "Net-(U3-IN1)") (class "Default")
      (node (ref "R7") (pin "1") (pinfunction "1_1") (pintype "passive"))
      (node (ref "U3") (pin "1") (pinfunction "IN1_1") (pintype "passive"))
    )
    (net (code "87") (name "Net-(U3-IN2)") (class "Default")
      (node (ref "R8") (pin "1") (pinfunction "1_1") (pintype "passive"))
      (node (ref "U3") (pin "2") (pinfunction "IN2_2") (pintype "passive"))
    )
    (net (code "88") (name "Net-(U4-RFIOP)") (class "Default")
      (node (ref "C17") (pin "2") (pinfunction "2_2") (pintype "passive"))
      (node (ref "C18") (pin "2") (pinfunction "2_2") (pintype "passive"))
      (node (ref "L3") (pin "2") (pinfunction "2_2") (pintype "passive"))
      (node (ref "U4") (pin "25") (pinfunction "RFIOP_25") (pintype "passive"))
    )
    (net (code "89") (name "Net-(U4-SWITCH)") (class "Default")
      (node (ref "L4") (pin "1") (pinfunction "1_1") (pintype "passive"))
      (node (ref "U4") (pin "23") (pinfunction "SWITCH_23") (pintype "passive"))
    )
    (net (code "90") (name "Net-(U4-VDD_FLASH)") (class "Default")
      (node (ref "C29") (pin "2") (pinfunction "2_2") (pintype "passive"))
      (node (ref "C30") (pin "1") (pinfunction "1_1") (pintype "passive"))
      (node (ref "U4") (pin "8") (pinfunction "VDD_FLASH_8") (pintype "passive"))
    )
    (net (code "91") (name "Net-(U4-VDD_PA)") (class "Default")
      (node (ref "L3") (pin "1") (pinfunction "1_1") (pintype "passive"))
      (node (ref "U4") (pin "26") (pinfunction "VDD_PA_26") (pintype "passive"))
    )
    (net (code "92") (name "Net-(U5-C1)") (class "Default")
      (node (ref "C24") (pin "1") (pinfunction "1_1") (pintype "passive"))
      (node (ref "U5") (pin "2") (pinfunction "C1_2") (pintype "passive"))
    )
    (net (code "93") (name "Net-(U5-CSEL)") (class "Default")
      (node (ref "C27") (pin "1") (pinfunction "1_1") (pintype "passive"))
      (node (ref "U5") (pin "3") (pinfunction "CSEL_3") (pintype "passive"))
    )
    (net (code "94") (name "Net-(U5-KEY2)") (class "Default")
      (node (ref "R27") (pin "1") (pinfunction "1_1") (pintype "passive"))
      (node (ref "U5") (pin "5") (pinfunction "KEY2_5") (pintype "passive"))
    )
    (net (code "95") (name "Net-(U5-KEY3)") (class "Default")
      (node (ref "R25") (pin "1") (pinfunction "1_1") (pintype "passive"))
      (node (ref "U5") (pin "6") (pinfunction "KEY3_6") (pintype "passive"))
    )
    (net (code "96") (name "Net-(U5-KEY4)") (class "Default")
      (node (ref "R22") (pin "1") (pinfunction "1_1") (pintype "passive"))
      (node (ref "U5") (pin "7") (pinfunction "KEY4_7") (pintype "passive"))
    )
    (net (code "97") (name "Net-(U5-KEY5)") (class "Default")
      (node (ref "R20") (pin "1") (pinfunction "1_1") (pintype "passive"))
      (node (ref "U5") (pin "8") (pinfunction "KEY5_8") (pintype "passive"))
    )
    (net (code "98") (name "Net-(U5-MD)") (class "Default")
      (node (ref "R29") (pin "2") (pinfunction "2_2") (pintype "passive"))
      (node (ref "U5") (pin "15") (pinfunction "MD_15") (pintype "passive"))
    )
    (net (code "99") (name "Net-(U5-VDD)") (class "Default")
      (node (ref "C25") (pin "1") (pinfunction "1_1") (pintype "passive"))
      (node (ref "C26") (pin "1") (pinfunction "1_1") (pintype "passive"))
      (node (ref "R21") (pin "2") (pinfunction "2_2") (pintype "passive"))
      (node (ref "R29") (pin "1") (pinfunction "1_1") (pintype "passive"))
      (node (ref "U5") (pin "16") (pinfunction "VDD_16") (pintype "passive"))
    )
    (net (code "100") (name "VCC") (class "Default")
      (node (ref "C7") (pin "2") (pinfunction "2_2") (pintype "passive"))
      (node (ref "C8") (pin "2") (pinfunction "2_2") (pintype "passive"))
      (node (ref "D1") (pin "2") (pinfunction "K_2") (pintype "passive"))
      (node (ref "R6") (pin "1") (pinfunction "1_1") (pintype "passive"))
      (node (ref "U2") (pin "6") (pinfunction "VDD_6") (pintype "passive"))
      (node (ref "VCC") (pin "1") (pinfunction "1_1") (pintype "passive"))
    )
    (net (code "101") (name "VCC3.3V") (class "Default")
      (node (ref "D10") (pin "1") (pinfunction "A_1") (pintype "passive"))
      (node (ref "D3") (pin "2") (pinfunction "K_2") (pintype "passive"))
      (node (ref "D4") (pin "2") (pinfunction "K_2") (pintype "passive"))
      (node (ref "D9") (pin "2") (pinfunction "K_2") (pintype "passive"))
      (node (ref "JP1") (pin "1") (pinfunction "1_1") (pintype "passive"))
      (node (ref "JP5") (pin "3") (pinfunction "3_3") (pintype "passive"))
      (node (ref "R16") (pin "1") (pinfunction "1_1") (pintype "passive"))
      (node (ref "R17") (pin "1") (pinfunction "1_1") (pintype "passive"))
      (node (ref "R21") (pin "1") (pinfunction "1_1") (pintype "passive"))
      (node (ref "R24") (pin "1") (pintype "passive"))
      (node (ref "R26") (pin "1") (pintype "passive"))
      (node (ref "VDD") (pin "1") (pinfunction "1_1") (pintype "passive"))
    )
    (net (code "102") (name "unconnected-(U2-BZ-Pad7)") (class "Default")
      (node (ref "U2") (pin "7") (pinfunction "BZ_7") (pintype "passive"))
    )
    (net (code "103") (name "unconnected-(U2-BZN-Pad8)") (class "Default")
      (node (ref "U2") (pin "8") (pinfunction "BZN_8") (pintype "passive"))
    )
    (net (code "104") (name "unconnected-(U2-SEG18-Pad26)") (class "Default")
      (node (ref "U2") (pin "26") (pinfunction "SEG18_26") (pintype "passive"))
    )
    (net (code "105") (name "unconnected-(U2-SEG19-Pad25)") (class "Default")
      (node (ref "U2") (pin "25") (pinfunction "SEG19_25") (pintype "passive"))
    )
    (net (code "106") (name "unconnected-(U2-SEG20-Pad24)") (class "Default")
      (node (ref "U2") (pin "24") (pinfunction "SEG20_24") (pintype "passive"))
    )
    (net (code "107") (name "unconnected-(U2-SEG21-Pad23)") (class "Default")
      (node (ref "U2") (pin "23") (pinfunction "SEG21_23") (pintype "passive"))
    )
    (net (code "108") (name "unconnected-(U2-SEG22-Pad22)") (class "Default")
      (node (ref "U2") (pin "22") (pinfunction "SEG22_22") (pintype "passive"))
    )
    (net (code "109") (name "unconnected-(U2-SEG23-Pad21)") (class "Default")
      (node (ref "U2") (pin "21") (pinfunction "SEG23_21") (pintype "passive"))
    )
    (net (code "110") (name "unconnected-(U2-SEG24-Pad20)") (class "Default")
      (node (ref "U2") (pin "20") (pinfunction "SEG24_20") (pintype "passive"))
    )
    (net (code "111") (name "unconnected-(U2-SEG25-Pad19)") (class "Default")
      (node (ref "U2") (pin "19") (pinfunction "SEG25_19") (pintype "passive"))
    )
    (net (code "112") (name "unconnected-(U2-SEG26-Pad18)") (class "Default")
      (node (ref "U2") (pin "18") (pinfunction "SEG26_18") (pintype "passive"))
    )
    (net (code "113") (name "unconnected-(U2-SEG27-Pad17)") (class "Default")
      (node (ref "U2") (pin "17") (pinfunction "SEG27_17") (pintype "passive"))
    )
    (net (code "114") (name "unconnected-(U2-SEG28-Pad16)") (class "Default")
      (node (ref "U2") (pin "16") (pinfunction "SEG28_16") (pintype "passive"))
    )
    (net (code "115") (name "unconnected-(U2-SEG29-Pad15)") (class "Default")
      (node (ref "U2") (pin "15") (pinfunction "SEG29_15") (pintype "passive"))
    )
    (net (code "116") (name "unconnected-(U2-SEG30-Pad14)") (class "Default")
      (node (ref "U2") (pin "14") (pinfunction "SEG30_14") (pintype "passive"))
    )
    (net (code "117") (name "unconnected-(U2-SEG31-Pad13)") (class "Default")
      (node (ref "U2") (pin "13") (pinfunction "SEG31_13") (pintype "passive"))
    )
    (net (code "118") (name "unconnected-(U5-KEY1-Pad4)") (class "Default")
      (node (ref "U5") (pin "4") (pinfunction "KEY1_4") (pintype "passive"))
    )
    (net (code "119") (name "unconnected-(U5-OUT1-Pad13)") (class "Default")
      (node (ref "U5") (pin "13") (pinfunction "OUT1_13") (pintype "passive"))
    )
  )
)
